# output_stage_sn74hc595n.net
KiCad netlist of a schematic drawn in EAGLE
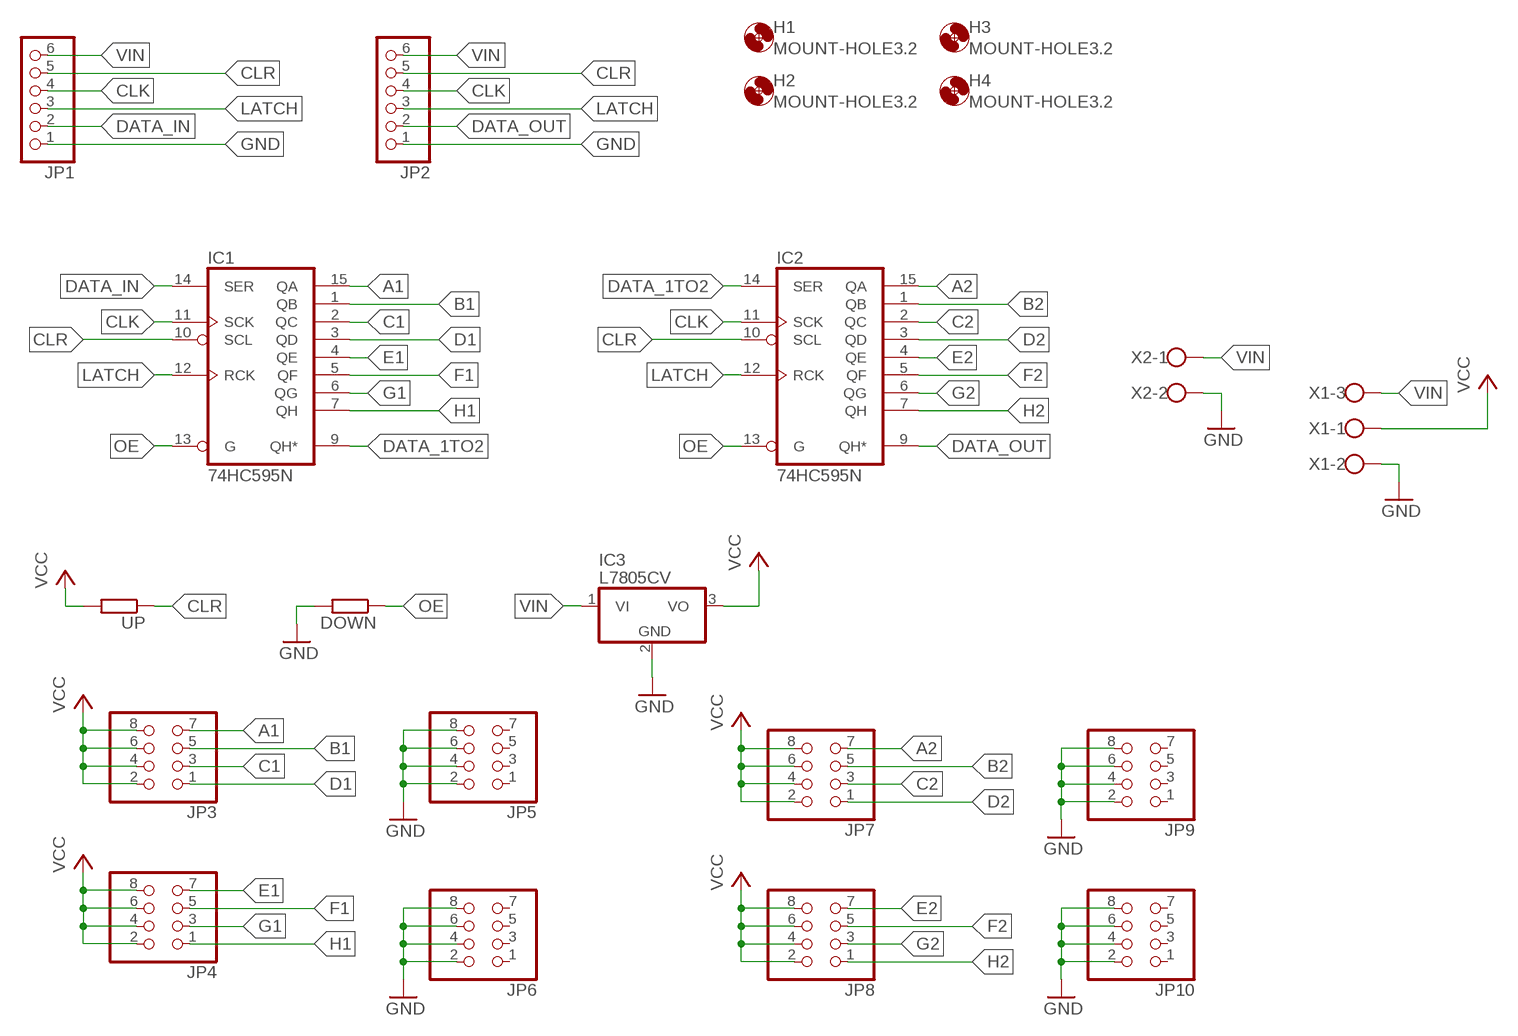
[diagram p0: schematic, sheet 1]

(export (version "E")
  (design (tool "Eeschema 10.0.6"))
  (components
    (comp (ref "DOWN")
      (value "R-EU_0207/10")
      (footprint "eagle-import:0207_10")
      (libsource (lib "eagle-import") (part "R-EU_0207/10"))
    )
    (comp (ref "H1")
      (value "MOUNT-HOLE3.2")
      (footprint "eagle-import:3,2")
      (libsource (lib "eagle-import") (part "MOUNT-HOLE3.2"))
    )
    (comp (ref "H2")
      (value "MOUNT-HOLE3.2")
      (footprint "eagle-import:3,2")
      (libsource (lib "eagle-import") (part "MOUNT-HOLE3.2"))
    )
    (comp (ref "H3")
      (value "MOUNT-HOLE3.2")
      (footprint "eagle-import:3,2")
      (libsource (lib "eagle-import") (part "MOUNT-HOLE3.2"))
    )
    (comp (ref "H4")
      (value "MOUNT-HOLE3.2")
      (footprint "eagle-import:3,2")
      (libsource (lib "eagle-import") (part "MOUNT-HOLE3.2"))
    )
    (comp (ref "IC1")
      (value "74HC595N")
      (footprint "eagle-import:DIL16")
      (libsource (lib "eagle-import") (part "74595NHC"))
    )
    (comp (ref "IC2")
      (value "74HC595N")
      (footprint "eagle-import:DIL16")
      (libsource (lib "eagle-import") (part "74595NHC"))
    )
    (comp (ref "IC3")
      (value "L7805CV")
      (footprint "eagle-import:TO220V")
      (libsource (lib "eagle-import") (part "78TV05"))
    )
    (comp (ref "JP1")
      (value "PINHD-1X6")
      (footprint "eagle-import:1X06")
      (libsource (lib "eagle-import") (part "PINHD-1X6"))
    )
    (comp (ref "JP2")
      (value "PINHD-1X6")
      (footprint "eagle-import:1X06")
      (libsource (lib "eagle-import") (part "PINHD-1X6"))
    )
    (comp (ref "JP3")
      (value "PINHD-2X4")
      (footprint "eagle-import:2X04")
      (libsource (lib "eagle-import") (part "PINHD-2X4"))
    )
    (comp (ref "JP4")
      (value "PINHD-2X4")
      (footprint "eagle-import:2X04")
      (libsource (lib "eagle-import") (part "PINHD-2X4"))
    )
    (comp (ref "JP5")
      (value "PINHD-2X4")
      (footprint "eagle-import:2X04")
      (libsource (lib "eagle-import") (part "PINHD-2X4"))
    )
    (comp (ref "JP6")
      (value "PINHD-2X4")
      (footprint "eagle-import:2X04")
      (libsource (lib "eagle-import") (part "PINHD-2X4"))
    )
    (comp (ref "JP7")
      (value "PINHD-2X4")
      (footprint "eagle-import:2X04")
      (libsource (lib "eagle-import") (part "PINHD-2X4"))
    )
    (comp (ref "JP8")
      (value "PINHD-2X4")
      (footprint "eagle-import:2X04")
      (libsource (lib "eagle-import") (part "PINHD-2X4"))
    )
    (comp (ref "JP9")
      (value "PINHD-2X4")
      (footprint "eagle-import:2X04")
      (libsource (lib "eagle-import") (part "PINHD-2X4"))
    )
    (comp (ref "JP10")
      (value "PINHD-2X4")
      (footprint "eagle-import:2X04")
      (libsource (lib "eagle-import") (part "PINHD-2X4"))
    )
    (comp (ref "UP")
      (value "R-EU_0207/10")
      (footprint "eagle-import:0207_10")
      (libsource (lib "eagle-import") (part "R-EU_0207/10"))
    )
    (comp (ref "X1")
      (value "W237-103")
      (footprint "eagle-import:W237-103")
      (fields (field (name "MPN") "237-103"))
      (libsource (lib "eagle-import") (part "W237-103"))
    )
    (comp (ref "X2")
      (value "W237-102")
      (footprint "eagle-import:W237-102")
      (fields (field (name "MPN") "237-102"))
      (libsource (lib "eagle-import") (part "W237-102"))
    )
  )
  (nets
    (net (code "1") (name "A1") (class "Default")
      (node (ref "IC1") (pin "15") (pinfunction "QA_15") (pintype "tri_state"))
      (node (ref "JP3") (pin "7") (pinfunction "7_7") (pintype "passive"))
    )
    (net (code "2") (name "A2") (class "Default")
      (node (ref "IC2") (pin "15") (pinfunction "QA_15") (pintype "tri_state"))
      (node (ref "JP7") (pin "7") (pinfunction "7_7") (pintype "passive"))
    )
    (net (code "3") (name "B1") (class "Default")
      (node (ref "IC1") (pin "1") (pinfunction "QB_1") (pintype "tri_state"))
      (node (ref "JP3") (pin "5") (pinfunction "5_5") (pintype "passive"))
    )
    (net (code "4") (name "B2") (class "Default")
      (node (ref "IC2") (pin "1") (pinfunction "QB_1") (pintype "tri_state"))
      (node (ref "JP7") (pin "5") (pinfunction "5_5") (pintype "passive"))
    )
    (net (code "5") (name "C1") (class "Default")
      (node (ref "IC1") (pin "2") (pinfunction "QC_2") (pintype "tri_state"))
      (node (ref "JP3") (pin "3") (pinfunction "3_3") (pintype "passive"))
    )
    (net (code "6") (name "C2") (class "Default")
      (node (ref "IC2") (pin "2") (pinfunction "QC_2") (pintype "tri_state"))
      (node (ref "JP7") (pin "3") (pinfunction "3_3") (pintype "passive"))
    )
    (net (code "7") (name "CLK") (class "Default")
      (node (ref "IC1") (pin "11") (pinfunction "SCK_11") (pintype "input"))
      (node (ref "IC2") (pin "11") (pinfunction "SCK_11") (pintype "input"))
      (node (ref "JP1") (pin "4") (pinfunction "4_4") (pintype "passive"))
      (node (ref "JP2") (pin "4") (pinfunction "4_4") (pintype "passive"))
    )
    (net (code "8") (name "CLR") (class "Default")
      (node (ref "IC1") (pin "10") (pinfunction "SCL_10") (pintype "input"))
      (node (ref "IC2") (pin "10") (pinfunction "SCL_10") (pintype "input"))
      (node (ref "JP1") (pin "5") (pinfunction "5_5") (pintype "passive"))
      (node (ref "JP2") (pin "5") (pinfunction "5_5") (pintype "passive"))
      (node (ref "UP") (pin "1") (pinfunction "1_1") (pintype "passive"))
    )
    (net (code "9") (name "D1") (class "Default")
      (node (ref "IC1") (pin "3") (pinfunction "QD_3") (pintype "tri_state"))
      (node (ref "JP3") (pin "1") (pinfunction "1_1") (pintype "passive"))
    )
    (net (code "10") (name "D2") (class "Default")
      (node (ref "IC2") (pin "3") (pinfunction "QD_3") (pintype "tri_state"))
      (node (ref "JP7") (pin "1") (pinfunction "1_1") (pintype "passive"))
    )
    (net (code "11") (name "DATA_1TO2") (class "Default")
      (node (ref "IC1") (pin "9") (pinfunction "QH*_9") (pintype "tri_state"))
      (node (ref "IC2") (pin "14") (pinfunction "SER_14") (pintype "input"))
    )
    (net (code "12") (name "DATA_IN") (class "Default")
      (node (ref "IC1") (pin "14") (pinfunction "SER_14") (pintype "input"))
      (node (ref "JP1") (pin "2") (pinfunction "2_2") (pintype "passive"))
    )
    (net (code "13") (name "DATA_OUT") (class "Default")
      (node (ref "IC2") (pin "9") (pinfunction "QH*_9") (pintype "tri_state"))
      (node (ref "JP2") (pin "2") (pinfunction "2_2") (pintype "passive"))
    )
    (net (code "14") (name "E1") (class "Default")
      (node (ref "IC1") (pin "4") (pinfunction "QE_4") (pintype "tri_state"))
      (node (ref "JP4") (pin "7") (pinfunction "7_7") (pintype "passive"))
    )
    (net (code "15") (name "E2") (class "Default")
      (node (ref "IC2") (pin "4") (pinfunction "QE_4") (pintype "tri_state"))
      (node (ref "JP8") (pin "7") (pinfunction "7_7") (pintype "passive"))
    )
    (net (code "16") (name "F1") (class "Default")
      (node (ref "IC1") (pin "5") (pinfunction "QF_5") (pintype "tri_state"))
      (node (ref "JP4") (pin "5") (pinfunction "5_5") (pintype "passive"))
    )
    (net (code "17") (name "F2") (class "Default")
      (node (ref "IC2") (pin "5") (pinfunction "QF_5") (pintype "tri_state"))
      (node (ref "JP8") (pin "5") (pinfunction "5_5") (pintype "passive"))
    )
    (net (code "18") (name "G1") (class "Default")
      (node (ref "IC1") (pin "6") (pinfunction "QG_6") (pintype "tri_state"))
      (node (ref "JP4") (pin "3") (pinfunction "3_3") (pintype "passive"))
    )
    (net (code "19") (name "G2") (class "Default")
      (node (ref "IC2") (pin "6") (pinfunction "QG_6") (pintype "tri_state"))
      (node (ref "JP8") (pin "3") (pinfunction "3_3") (pintype "passive"))
    )
    (net (code "20") (name "GND") (class "Default")
      (node (ref "DOWN") (pin "2") (pinfunction "2_2") (pintype "passive"))
      (node (ref "IC3") (pin "2") (pinfunction "GND_2") (pintype "passive"))
      (node (ref "JP1") (pin "1") (pinfunction "1_1") (pintype "passive"))
      (node (ref "JP10") (pin "2") (pinfunction "2_2") (pintype "passive"))
      (node (ref "JP10") (pin "4") (pinfunction "4_4") (pintype "passive"))
      (node (ref "JP10") (pin "6") (pinfunction "6_6") (pintype "passive"))
      (node (ref "JP10") (pin "8") (pinfunction "8_8") (pintype "passive"))
      (node (ref "JP2") (pin "1") (pinfunction "1_1") (pintype "passive"))
      (node (ref "JP5") (pin "2") (pinfunction "2_2") (pintype "passive"))
      (node (ref "JP5") (pin "4") (pinfunction "4_4") (pintype "passive"))
      (node (ref "JP5") (pin "6") (pinfunction "6_6") (pintype "passive"))
      (node (ref "JP5") (pin "8") (pinfunction "8_8") (pintype "passive"))
      (node (ref "JP6") (pin "2") (pinfunction "2_2") (pintype "passive"))
      (node (ref "JP6") (pin "4") (pinfunction "4_4") (pintype "passive"))
      (node (ref "JP6") (pin "6") (pinfunction "6_6") (pintype "passive"))
      (node (ref "JP6") (pin "8") (pinfunction "8_8") (pintype "passive"))
      (node (ref "JP9") (pin "2") (pinfunction "2_2") (pintype "passive"))
      (node (ref "JP9") (pin "4") (pinfunction "4_4") (pintype "passive"))
      (node (ref "JP9") (pin "6") (pinfunction "6_6") (pintype "passive"))
      (node (ref "JP9") (pin "8") (pinfunction "8_8") (pintype "passive"))
      (node (ref "X1") (pin "2") (pinfunction "KL_2") (pintype "passive"))
      (node (ref "X2") (pin "2") (pinfunction "KL_2") (pintype "passive"))
    )
    (net (code "21") (name "H1") (class "Default")
      (node (ref "IC1") (pin "7") (pinfunction "QH_7") (pintype "tri_state"))
      (node (ref "JP4") (pin "1") (pinfunction "1_1") (pintype "passive"))
    )
    (net (code "22") (name "H2") (class "Default")
      (node (ref "IC2") (pin "7") (pinfunction "QH_7") (pintype "tri_state"))
      (node (ref "JP8") (pin "1") (pinfunction "1_1") (pintype "passive"))
    )
    (net (code "23") (name "LATCH") (class "Default")
      (node (ref "IC1") (pin "12") (pinfunction "RCK_12") (pintype "input"))
      (node (ref "IC2") (pin "12") (pinfunction "RCK_12") (pintype "input"))
      (node (ref "JP1") (pin "3") (pinfunction "3_3") (pintype "passive"))
      (node (ref "JP2") (pin "3") (pinfunction "3_3") (pintype "passive"))
    )
    (net (code "24") (name "OE") (class "Default")
      (node (ref "DOWN") (pin "1") (pinfunction "1_1") (pintype "passive"))
      (node (ref "IC1") (pin "13") (pinfunction "G_13") (pintype "input"))
      (node (ref "IC2") (pin "13") (pinfunction "G_13") (pintype "input"))
    )
    (net (code "25") (name "VCC") (class "Default")
      (node (ref "IC3") (pin "3") (pinfunction "VO_3") (pintype "passive"))
      (node (ref "JP3") (pin "2") (pinfunction "2_2") (pintype "passive"))
      (node (ref "JP3") (pin "4") (pinfunction "4_4") (pintype "passive"))
      (node (ref "JP3") (pin "6") (pinfunction "6_6") (pintype "passive"))
      (node (ref "JP3") (pin "8") (pinfunction "8_8") (pintype "passive"))
      (node (ref "JP4") (pin "2") (pinfunction "2_2") (pintype "passive"))
      (node (ref "JP4") (pin "4") (pinfunction "4_4") (pintype "passive"))
      (node (ref "JP4") (pin "6") (pinfunction "6_6") (pintype "passive"))
      (node (ref "JP4") (pin "8") (pinfunction "8_8") (pintype "passive"))
      (node (ref "JP7") (pin "2") (pinfunction "2_2") (pintype "passive"))
      (node (ref "JP7") (pin "4") (pinfunction "4_4") (pintype "passive"))
      (node (ref "JP7") (pin "6") (pinfunction "6_6") (pintype "passive"))
      (node (ref "JP7") (pin "8") (pinfunction "8_8") (pintype "passive"))
      (node (ref "JP8") (pin "2") (pinfunction "2_2") (pintype "passive"))
      (node (ref "JP8") (pin "4") (pinfunction "4_4") (pintype "passive"))
      (node (ref "JP8") (pin "6") (pinfunction "6_6") (pintype "passive"))
      (node (ref "JP8") (pin "8") (pinfunction "8_8") (pintype "passive"))
      (node (ref "UP") (pin "2") (pinfunction "2_2") (pintype "passive"))
      (node (ref "X1") (pin "1") (pinfunction "KL_1") (pintype "passive"))
    )
    (net (code "26") (name "VIN") (class "Default")
      (node (ref "IC3") (pin "1") (pinfunction "VI_1") (pintype "input"))
      (node (ref "JP1") (pin "6") (pinfunction "6_6") (pintype "passive"))
      (node (ref "JP2") (pin "6") (pinfunction "6_6") (pintype "passive"))
      (node (ref "X1") (pin "3") (pinfunction "KL_3") (pintype "passive"))
      (node (ref "X2") (pin "1") (pinfunction "KL_1") (pintype "passive"))
    )
    (net (code "27") (name "unconnected-(JP5-Pad1)") (class "Default")
      (node (ref "JP5") (pin "1") (pinfunction "1_1") (pintype "passive"))
    )
    (net (code "28") (name "unconnected-(JP5-Pad3)") (class "Default")
      (node (ref "JP5") (pin "3") (pinfunction "3_3") (pintype "passive"))
    )
    (net (code "29") (name "unconnected-(JP5-Pad5)") (class "Default")
      (node (ref "JP5") (pin "5") (pinfunction "5_5") (pintype "passive"))
    )
    (net (code "30") (name "unconnected-(JP5-Pad7)") (class "Default")
      (node (ref "JP5") (pin "7") (pinfunction "7_7") (pintype "passive"))
    )
    (net (code "31") (name "unconnected-(JP6-Pad1)") (class "Default")
      (node (ref "JP6") (pin "1") (pinfunction "1_1") (pintype "passive"))
    )
    (net (code "32") (name "unconnected-(JP6-Pad3)") (class "Default")
      (node (ref "JP6") (pin "3") (pinfunction "3_3") (pintype "passive"))
    )
    (net (code "33") (name "unconnected-(JP6-Pad5)") (class "Default")
      (node (ref "JP6") (pin "5") (pinfunction "5_5") (pintype "passive"))
    )
    (net (code "34") (name "unconnected-(JP6-Pad7)") (class "Default")
      (node (ref "JP6") (pin "7") (pinfunction "7_7") (pintype "passive"))
    )
    (net (code "35") (name "unconnected-(JP9-Pad1)") (class "Default")
      (node (ref "JP9") (pin "1") (pinfunction "1_1") (pintype "passive"))
    )
    (net (code "36") (name "unconnected-(JP9-Pad3)") (class "Default")
      (node (ref "JP9") (pin "3") (pinfunction "3_3") (pintype "passive"))
    )
    (net (code "37") (name "unconnected-(JP9-Pad5)") (class "Default")
      (node (ref "JP9") (pin "5") (pinfunction "5_5") (pintype "passive"))
    )
    (net (code "38") (name "unconnected-(JP9-Pad7)") (class "Default")
      (node (ref "JP9") (pin "7") (pinfunction "7_7") (pintype "passive"))
    )
    (net (code "39") (name "unconnected-(JP10-Pad1)") (class "Default")
      (node (ref "JP10") (pin "1") (pinfunction "1_1") (pintype "passive"))
    )
    (net (code "40") (name "unconnected-(JP10-Pad3)") (class "Default")
      (node (ref "JP10") (pin "3") (pinfunction "3_3") (pintype "passive"))
    )
    (net (code "41") (name "unconnected-(JP10-Pad5)") (class "Default")
      (node (ref "JP10") (pin "5") (pinfunction "5_5") (pintype "passive"))
    )
    (net (code "42") (name "unconnected-(JP10-Pad7)") (class "Default")
      (node (ref "JP10") (pin "7") (pinfunction "7_7") (pintype "passive"))
    )
  )
)
